# sendai.net
KiCad netlist of a schematic drawn in EAGLE
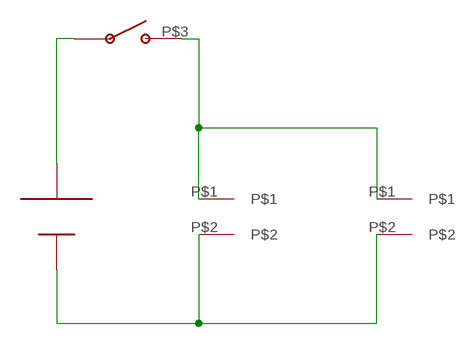
[diagram p0: schematic, sheet 1]

(export (version "E")
  (design (tool "Eeschema 10.0.6"))
  (components
    (comp (ref "U$1")
      (value "CR2032")
      (footprint "eagle-import:CR2032")
      (libsource (lib "eagle-import") (part "CR2032"))
    )
    (comp (ref "U$2")
      (value "CON2")
      (footprint "eagle-import:CON2")
      (libsource (lib "eagle-import") (part "CON2"))
    )
    (comp (ref "U$3")
      (value "CON2")
      (footprint "eagle-import:CON2")
      (libsource (lib "eagle-import") (part "CON2"))
    )
    (comp (ref "U$4")
      (value "LEAD_SWITCH")
      (footprint "eagle-import:LEAD_SWITCH")
      (libsource (lib "eagle-import") (part "LEAD_SWITCH"))
    )
  )
  (nets
    (net (code "1") (name "Net-(U$1-+)") (class "Default")
      (node (ref "U$1") (pin "+1") (pinfunction "+_+1") (pintype "bidirectional"))
      (node (ref "U$4") (pin "P$4") (pinfunction "P$2_P$4") (pintype "bidirectional"))
    )
    (net (code "2") (name "Net-(U$1--)") (class "Default")
      (node (ref "U$1") (pin "-1") (pinfunction "-_-1") (pintype "bidirectional"))
      (node (ref "U$2") (pin "P$2") (pinfunction "P$2_P$2") (pintype "bidirectional"))
      (node (ref "U$3") (pin "P$2") (pinfunction "P$2_P$2") (pintype "bidirectional"))
    )
    (net (code "3") (name "Net-(U$4-P$1)") (class "Default")
      (node (ref "U$2") (pin "P$1") (pinfunction "P$1_P$1") (pintype "bidirectional"))
      (node (ref "U$3") (pin "P$1") (pinfunction "P$1_P$1") (pintype "bidirectional"))
      (node (ref "U$4") (pin "P$3") (pinfunction "P$1_P$3") (pintype "bidirectional"))
    )
  )
)
